# InterfaceConfiguracao.net
KiCad netlist of a schematic drawn in Altium Designer
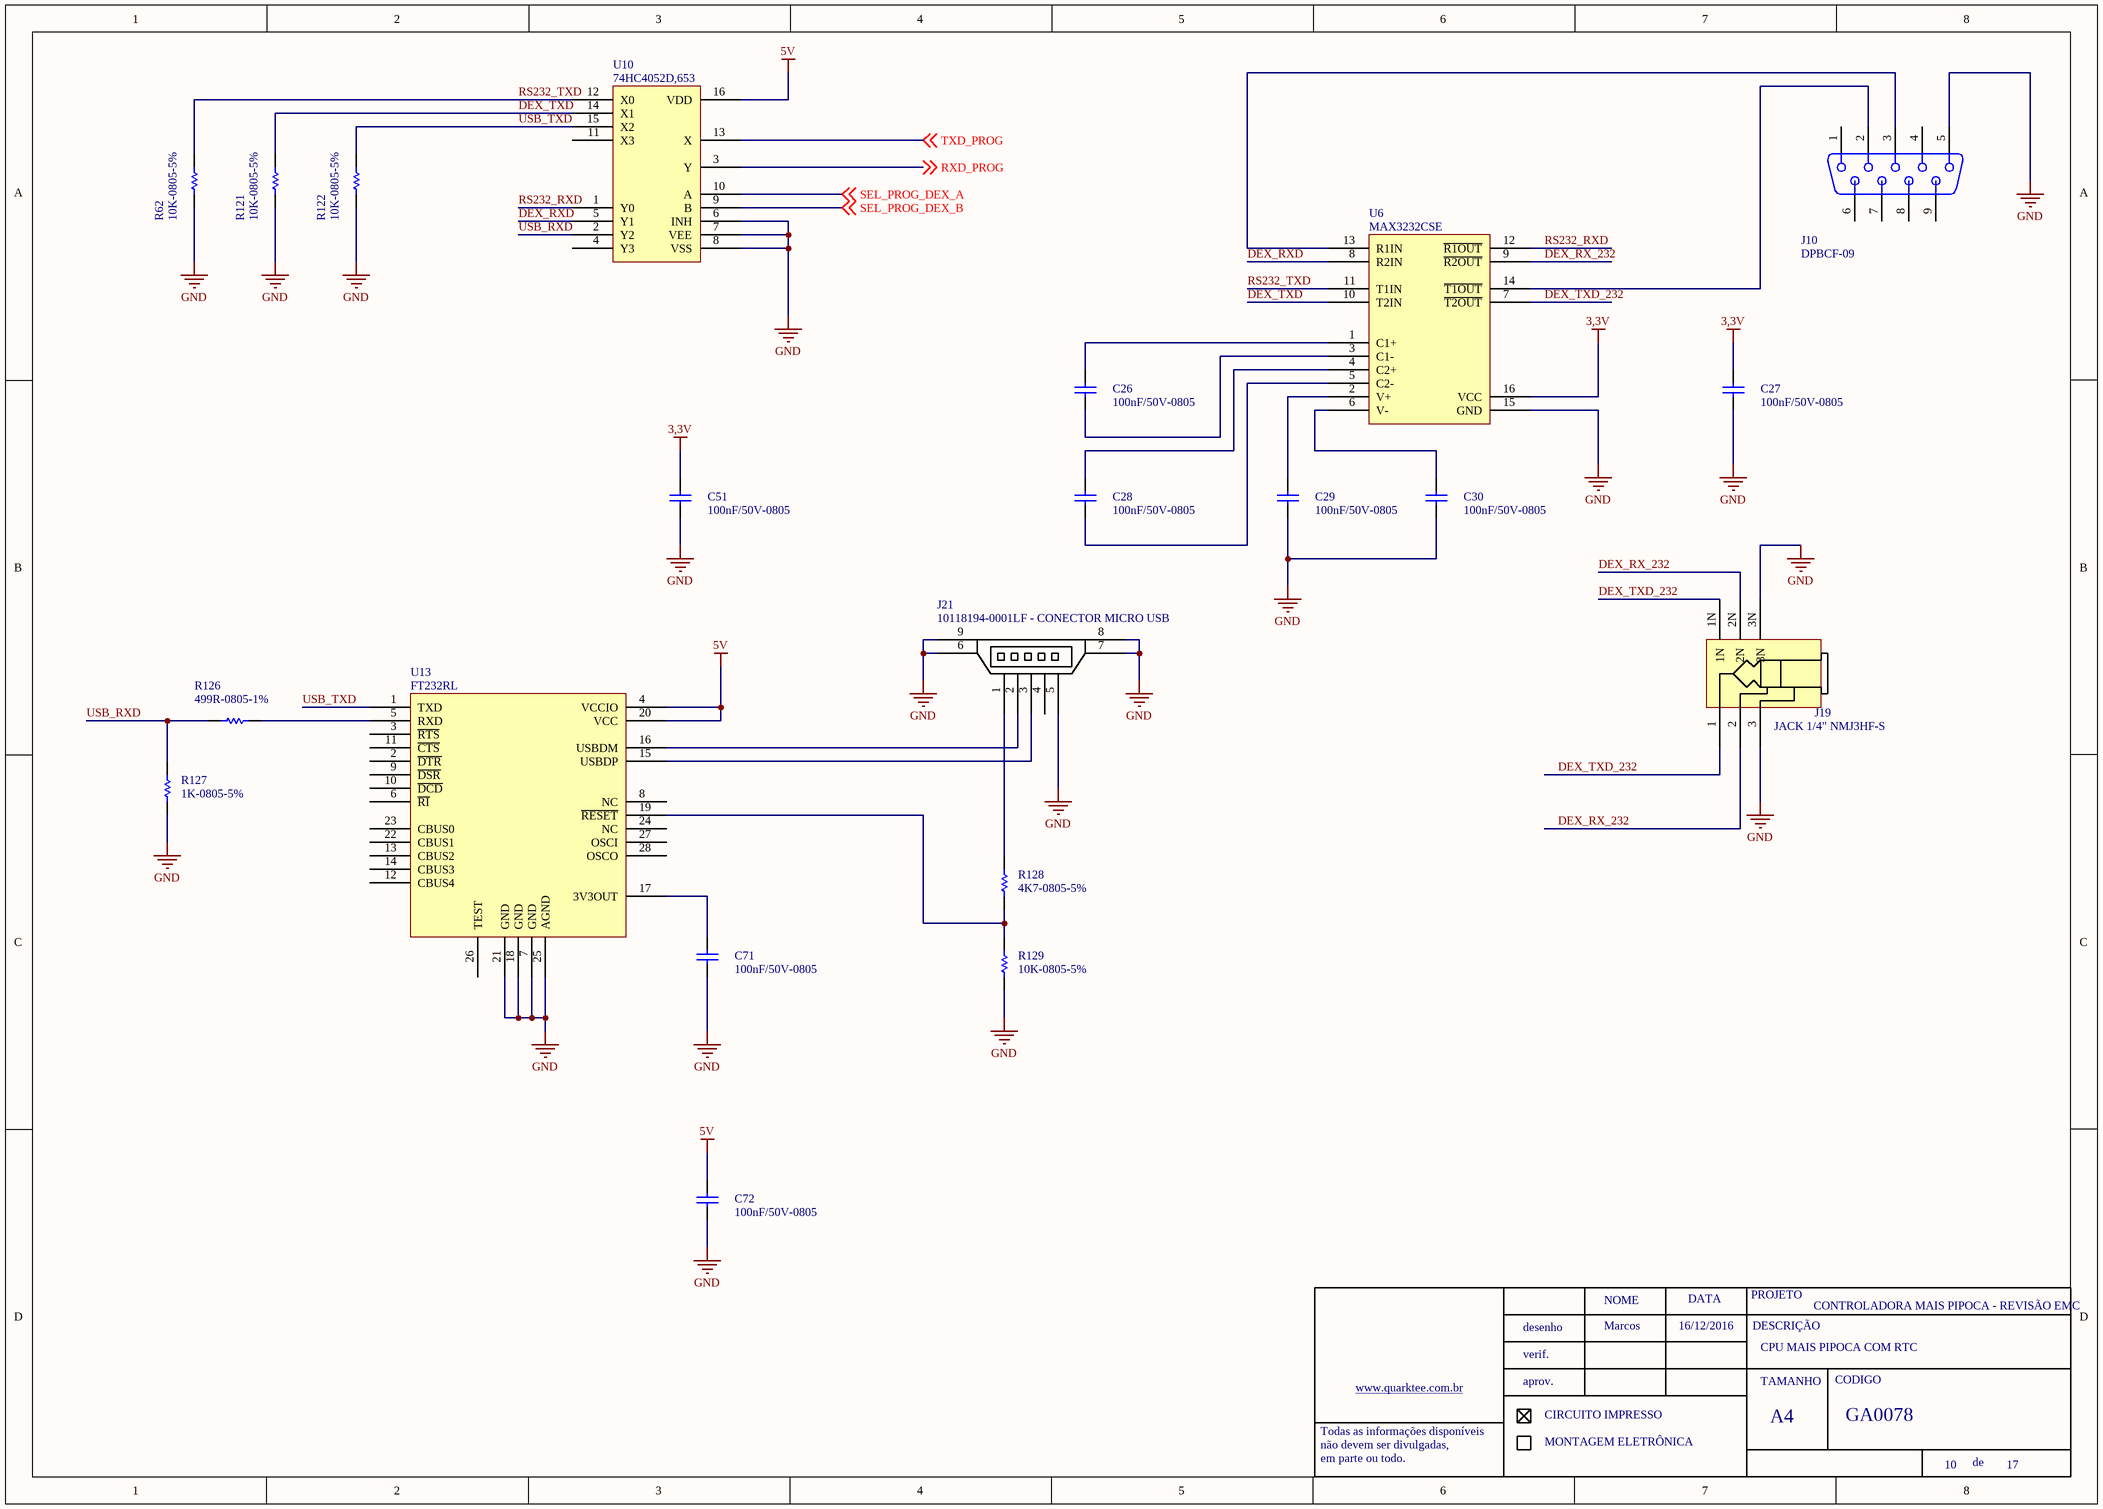
[diagram p0: InterfaceConfiguracao.SchDoc]

(export (version "E")
  (design (tool "Eeschema 10.0.6"))
  (components
    (comp (ref "C26")
      (value "100nF/50V-0805")
      (footprint "0805-REVISADO ONDA")
      (description "100nF/50-0805-NPO")
      (libsource (lib "AquinoLib") (part "100nF/50-0805-NPO"))
    )
    (comp (ref "C27")
      (value "100nF/50V-0805")
      (footprint "0805-REVISADO ONDA")
      (description "100nF/50-0805-NPO")
      (libsource (lib "AquinoLib") (part "100nF/50-0805-NPO"))
    )
    (comp (ref "C28")
      (value "100nF/50V-0805")
      (footprint "0805-REVISADO ONDA")
      (description "100nF/50-0805-NPO")
      (libsource (lib "AquinoLib") (part "100nF/50-0805-NPO"))
    )
    (comp (ref "C29")
      (value "100nF/50V-0805")
      (footprint "0805-REVISADO ONDA")
      (description "100nF/50-0805-NPO")
      (libsource (lib "AquinoLib") (part "100nF/50-0805-NPO"))
    )
    (comp (ref "C30")
      (value "100nF/50V-0805")
      (footprint "0805-REVISADO ONDA")
      (description "100nF/50-0805-NPO")
      (libsource (lib "AquinoLib") (part "100nF/50-0805-NPO"))
    )
    (comp (ref "C51")
      (value "100nF/50V-0805")
      (footprint "0805-REVISADO ONDA")
      (libsource (lib "AquinoLib") (part "100nF/50-0805-NPO"))
    )
    (comp (ref "C71")
      (value "100nF/50V-0805")
      (footprint "0805-REVISADO ONDA")
      (libsource (lib "AquinoLib") (part "100nF/50-0805-NPO"))
    )
    (comp (ref "C72")
      (value "100nF/50V-0805")
      (footprint "0805-REVISADO ONDA")
      (libsource (lib "AquinoLib") (part "100nF/50-0805-NPO"))
    )
    (comp (ref "J10")
      (value "DPBCF-09")
      (footprint "DB9-FÊMEA MONTAGEM EM PCI 180")
      (description "DBPCF-09")
      (libsource (lib "ChaveDigital3") (part "DB-9 - FÊMEA 180º MONTAGEM EM PCI"))
    )
    (comp (ref "J19")
      (value "JACK 1/4\" NMJ3HF-S")
      (description "NMJ3HF-S")
      (libsource (lib "AquinoLib") (part "NMJ3HF-S"))
    )
    (comp (ref "J21")
      (value "10118194-0001LF - CONECTOR MICRO USB")
      (libsource (lib "AquinoLib") (part "MINI_USB"))
    )
    (comp (ref "R62")
      (value "10K-0805-5%")
      (footprint "0805-REVISADO ONDA")
      (libsource (lib "AquinoLib") (part "10K-0805-5%"))
    )
    (comp (ref "R121")
      (value "10K-0805-5%")
      (footprint "0805-REVISADO ONDA")
      (libsource (lib "AquinoLib") (part "10K-0805-5%"))
    )
    (comp (ref "R122")
      (value "10K-0805-5%")
      (footprint "0805-REVISADO ONDA")
      (libsource (lib "AquinoLib") (part "10K-0805-5%"))
    )
    (comp (ref "R126")
      (value "499R-0805-1%")
      (footprint "0805-REVISADO ONDA")
      (description "1K-0805-5%")
      (libsource (lib "AquinoLib") (part "1K-0805-5%"))
    )
    (comp (ref "R127")
      (value "1K-0805-5%")
      (footprint "0805-REVISADO ONDA")
      (libsource (lib "AquinoLib") (part "1K-0805-5%"))
    )
    (comp (ref "R128")
      (value "4K7-0805-5%")
      (footprint "0805-REVISADO ONDA")
      (description "10K-0805-5%")
      (libsource (lib "AquinoLib") (part "10K-0805-5%"))
    )
    (comp (ref "R129")
      (value "10K-0805-5%")
      (footprint "0805-REVISADO ONDA")
      (libsource (lib "AquinoLib") (part "10K-0805-5%"))
    )
    (comp (ref "U6")
      (value "MAX3232CSE")
      (footprint "SOIC 16 PINOS")
      (libsource (lib "ChaveDigital3") (part "MAX3232CSE"))
    )
    (comp (ref "U10") (value "74HC4052D,653") (libsource (lib "AquinoLib") (part "CD74HC4052PWR")))
    (comp (ref "U13") (value "FT232RL") (libsource (lib "AquinoLib") (part "FT232RL")))
  )
  (nets
    (net (code "1") (name "/DEX_RXD") (class "Default")
      (node (ref "U10") (pin "5") (pinfunction "Y1_5") (pintype "passive"))
      (node (ref "U6") (pin "8") (pinfunction "R2IN_8") (pintype "passive"))
    )
    (net (code "2") (name "/DEX_RX_232") (class "Default")
      (node (ref "J19") (pin "2") (pinfunction "2_2") (pintype "passive"))
      (node (ref "J19") (pin "2N") (pinfunction "2N_2N") (pintype "passive"))
      (node (ref "U6") (pin "9") (pinfunction "~{R2OUT}_9") (pintype "passive"))
    )
    (net (code "3") (name "/DEX_TXD") (class "Default")
      (node (ref "R121") (pin "2") (pinfunction "2_2") (pintype "passive"))
      (node (ref "U10") (pin "14") (pinfunction "X1_14") (pintype "passive"))
      (node (ref "U6") (pin "10") (pinfunction "T2IN_10") (pintype "passive"))
    )
    (net (code "4") (name "/DEX_TXD_232") (class "Default")
      (node (ref "J19") (pin "1") (pinfunction "1_1") (pintype "passive"))
      (node (ref "J19") (pin "1N") (pinfunction "1N_1N") (pintype "passive"))
      (node (ref "U6") (pin "7") (pinfunction "~{T2OUT}_7") (pintype "passive"))
    )
    (net (code "5") (name "/RS232_RXD") (class "Default")
      (node (ref "U10") (pin "1") (pinfunction "Y0_1") (pintype "passive"))
      (node (ref "U6") (pin "12") (pinfunction "~{R1OUT}_12") (pintype "passive"))
    )
    (net (code "6") (name "/RS232_TXD") (class "Default")
      (node (ref "R62") (pin "2") (pinfunction "2_2") (pintype "passive"))
      (node (ref "U10") (pin "12") (pinfunction "X0_12") (pintype "passive"))
      (node (ref "U6") (pin "11") (pinfunction "T1IN_11") (pintype "passive"))
    )
    (net (code "7") (name "/USB_RXD") (class "Default")
      (node (ref "R126") (pin "1") (pinfunction "1_1") (pintype "passive"))
      (node (ref "R127") (pin "2") (pinfunction "2_2") (pintype "passive"))
      (node (ref "U10") (pin "2") (pinfunction "Y2_2") (pintype "passive"))
    )
    (net (code "8") (name "/USB_TXD") (class "Default")
      (node (ref "R122") (pin "2") (pinfunction "2_2") (pintype "passive"))
      (node (ref "U10") (pin "15") (pinfunction "X2_15") (pintype "passive"))
      (node (ref "U13") (pin "1") (pinfunction "TXD_1") (pintype "passive"))
    )
    (net (code "9") (name "3,3V") (class "Default")
      (node (ref "C27") (pin "2") (pinfunction "2_2") (pintype "passive"))
      (node (ref "C51") (pin "2") (pinfunction "2_2") (pintype "passive"))
      (node (ref "U6") (pin "16") (pinfunction "VCC_16") (pintype "passive"))
    )
    (net (code "10") (name "5V") (class "Default")
      (node (ref "C72") (pin "2") (pinfunction "2_2") (pintype "passive"))
      (node (ref "U10") (pin "16") (pinfunction "VDD_16") (pintype "passive"))
      (node (ref "U13") (pin "20") (pinfunction "VCC_20") (pintype "passive"))
      (node (ref "U13") (pin "4") (pinfunction "VCCIO_4") (pintype "passive"))
    )
    (net (code "11") (name "GND") (class "Default")
      (node (ref "C27") (pin "1") (pinfunction "1_1") (pintype "passive"))
      (node (ref "C29") (pin "1") (pinfunction "1_1") (pintype "passive"))
      (node (ref "C30") (pin "1") (pinfunction "1_1") (pintype "passive"))
      (node (ref "C51") (pin "1") (pinfunction "1_1") (pintype "passive"))
      (node (ref "C71") (pin "1") (pinfunction "1_1") (pintype "passive"))
      (node (ref "C72") (pin "1") (pinfunction "1_1") (pintype "passive"))
      (node (ref "J10") (pin "5") (pinfunction "5_5") (pintype "passive"))
      (node (ref "J19") (pin "3") (pinfunction "3_3") (pintype "passive"))
      (node (ref "J19") (pin "3N") (pinfunction "3N_3N") (pintype "passive"))
      (node (ref "J21") (pin "5") (pinfunction "5_5") (pintype "passive"))
      (node (ref "J21") (pin "6") (pinfunction "6_6") (pintype "passive"))
      (node (ref "J21") (pin "7") (pinfunction "7_7") (pintype "passive"))
      (node (ref "J21") (pin "8") (pinfunction "8_8") (pintype "passive"))
      (node (ref "J21") (pin "9") (pinfunction "9_9") (pintype "passive"))
      (node (ref "R121") (pin "1") (pinfunction "1_1") (pintype "passive"))
      (node (ref "R122") (pin "1") (pinfunction "1_1") (pintype "passive"))
      (node (ref "R127") (pin "1") (pinfunction "1_1") (pintype "passive"))
      (node (ref "R129") (pin "1") (pinfunction "1_1") (pintype "passive"))
      (node (ref "R62") (pin "1") (pinfunction "1_1") (pintype "passive"))
      (node (ref "U10") (pin "6") (pinfunction "INH_6") (pintype "passive"))
      (node (ref "U10") (pin "7") (pinfunction "VEE_7") (pintype "passive"))
      (node (ref "U10") (pin "8") (pinfunction "VSS_8") (pintype "passive"))
      (node (ref "U13") (pin "18") (pinfunction "GND_18") (pintype "passive"))
      (node (ref "U13") (pin "21") (pinfunction "GND_21") (pintype "passive"))
      (node (ref "U13") (pin "25") (pinfunction "AGND_25") (pintype "passive"))
      (node (ref "U13") (pin "7") (pinfunction "GND_7") (pintype "passive"))
      (node (ref "U6") (pin "15") (pinfunction "GND_15") (pintype "passive"))
    )
    (net (code "12") (name "Net-(J21-Pad1)") (class "Default")
      (node (ref "J21") (pin "1") (pinfunction "1_1") (pintype "passive"))
      (node (ref "R128") (pin "2") (pinfunction "2_2") (pintype "passive"))
    )
    (net (code "13") (name "Net-(U6-C1+)") (class "Default")
      (node (ref "C26") (pin "2") (pinfunction "2_2") (pintype "passive"))
      (node (ref "U6") (pin "1") (pinfunction "C1+_1") (pintype "passive"))
    )
    (net (code "14") (name "Net-(U6-C1-)") (class "Default")
      (node (ref "C26") (pin "1") (pinfunction "1_1") (pintype "passive"))
      (node (ref "U6") (pin "3") (pinfunction "C1-_3") (pintype "passive"))
    )
    (net (code "15") (name "Net-(U6-C2+)") (class "Default")
      (node (ref "C28") (pin "2") (pinfunction "2_2") (pintype "passive"))
      (node (ref "U6") (pin "4") (pinfunction "C2+_4") (pintype "passive"))
    )
    (net (code "16") (name "Net-(U6-C2-)") (class "Default")
      (node (ref "C28") (pin "1") (pinfunction "1_1") (pintype "passive"))
      (node (ref "U6") (pin "5") (pinfunction "C2-_5") (pintype "passive"))
    )
    (net (code "17") (name "Net-(U6-R1IN)") (class "Default")
      (node (ref "J10") (pin "3") (pinfunction "3_3") (pintype "passive"))
      (node (ref "U6") (pin "13") (pinfunction "R1IN_13") (pintype "passive"))
    )
    (net (code "18") (name "Net-(U6-V+)") (class "Default")
      (node (ref "C29") (pin "2") (pinfunction "2_2") (pintype "passive"))
      (node (ref "U6") (pin "2") (pinfunction "V+_2") (pintype "passive"))
    )
    (net (code "19") (name "Net-(U6-V-)") (class "Default")
      (node (ref "C30") (pin "2") (pinfunction "2_2") (pintype "passive"))
      (node (ref "U6") (pin "6") (pinfunction "V-_6") (pintype "passive"))
    )
    (net (code "20") (name "Net-(U6-~{T1OUT})") (class "Default")
      (node (ref "J10") (pin "2") (pinfunction "2_2") (pintype "passive"))
      (node (ref "U6") (pin "14") (pinfunction "~{T1OUT}_14") (pintype "passive"))
    )
    (net (code "21") (name "Net-(U13-3V3OUT)") (class "Default")
      (node (ref "C71") (pin "2") (pinfunction "2_2") (pintype "passive"))
      (node (ref "U13") (pin "17") (pinfunction "3V3OUT_17") (pintype "passive"))
    )
    (net (code "22") (name "Net-(U13-RXD)") (class "Default")
      (node (ref "R126") (pin "2") (pinfunction "2_2") (pintype "passive"))
      (node (ref "U13") (pin "5") (pinfunction "RXD_5") (pintype "passive"))
    )
    (net (code "23") (name "Net-(U13-USBDM)") (class "Default")
      (node (ref "J21") (pin "2") (pinfunction "2_2") (pintype "passive"))
      (node (ref "U13") (pin "16") (pinfunction "USBDM_16") (pintype "passive"))
    )
    (net (code "24") (name "Net-(U13-USBDP)") (class "Default")
      (node (ref "J21") (pin "3") (pinfunction "3_3") (pintype "passive"))
      (node (ref "U13") (pin "15") (pinfunction "USBDP_15") (pintype "passive"))
    )
    (net (code "25") (name "Net-(U13-~{RESET})") (class "Default")
      (node (ref "R128") (pin "1") (pinfunction "1_1") (pintype "passive"))
      (node (ref "R129") (pin "2") (pinfunction "2_2") (pintype "passive"))
      (node (ref "U13") (pin "19") (pinfunction "~{RESET}_19") (pintype "passive"))
    )
    (net (code "26") (name "RXD_PROG") (class "Default")
      (node (ref "U10") (pin "3") (pinfunction "Y_3") (pintype "passive"))
    )
    (net (code "27") (name "SEL_PROG_DEX_A") (class "Default")
      (node (ref "U10") (pin "10") (pinfunction "A_10") (pintype "passive"))
    )
    (net (code "28") (name "SEL_PROG_DEX_B") (class "Default")
      (node (ref "U10") (pin "9") (pinfunction "B_9") (pintype "passive"))
    )
    (net (code "29") (name "TXD_PROG") (class "Default")
      (node (ref "U10") (pin "13") (pinfunction "X_13") (pintype "passive"))
    )
    (net (code "30") (name "unconnected-(J10-Pad1)") (class "Default")
      (node (ref "J10") (pin "1") (pinfunction "1_1") (pintype "passive"))
    )
    (net (code "31") (name "unconnected-(J10-Pad4)") (class "Default")
      (node (ref "J10") (pin "4") (pinfunction "4_4") (pintype "passive"))
    )
    (net (code "32") (name "unconnected-(J10-Pad6)") (class "Default")
      (node (ref "J10") (pin "6") (pinfunction "6_6") (pintype "passive"))
    )
    (net (code "33") (name "unconnected-(J10-Pad7)") (class "Default")
      (node (ref "J10") (pin "7") (pinfunction "7_7") (pintype "passive"))
    )
    (net (code "34") (name "unconnected-(J10-Pad8)") (class "Default")
      (node (ref "J10") (pin "8") (pinfunction "8_8") (pintype "passive"))
    )
    (net (code "35") (name "unconnected-(J10-Pad9)") (class "Default")
      (node (ref "J10") (pin "9") (pinfunction "9_9") (pintype "passive"))
    )
    (net (code "36") (name "unconnected-(J21-Pad4)") (class "Default")
      (node (ref "J21") (pin "4") (pinfunction "4_4") (pintype "passive"))
    )
    (net (code "37") (name "unconnected-(U10-X3-Pad11)") (class "Default")
      (node (ref "U10") (pin "11") (pinfunction "X3_11") (pintype "passive"))
    )
    (net (code "38") (name "unconnected-(U10-Y3-Pad4)") (class "Default")
      (node (ref "U10") (pin "4") (pinfunction "Y3_4") (pintype "passive"))
    )
    (net (code "39") (name "unconnected-(U13-CBUS0-Pad23)") (class "Default")
      (node (ref "U13") (pin "23") (pinfunction "CBUS0_23") (pintype "passive"))
    )
    (net (code "40") (name "unconnected-(U13-CBUS1-Pad22)") (class "Default")
      (node (ref "U13") (pin "22") (pinfunction "CBUS1_22") (pintype "passive"))
    )
    (net (code "41") (name "unconnected-(U13-CBUS2-Pad13)") (class "Default")
      (node (ref "U13") (pin "13") (pinfunction "CBUS2_13") (pintype "passive"))
    )
    (net (code "42") (name "unconnected-(U13-CBUS3-Pad14)") (class "Default")
      (node (ref "U13") (pin "14") (pinfunction "CBUS3_14") (pintype "passive"))
    )
    (net (code "43") (name "unconnected-(U13-CBUS4-Pad12)") (class "Default")
      (node (ref "U13") (pin "12") (pinfunction "CBUS4_12") (pintype "passive"))
    )
    (net (code "44") (name "unconnected-(U13-NC-Pad8)") (class "Default")
      (node (ref "U13") (pin "8") (pinfunction "NC_8") (pintype "passive"))
    )
    (net (code "45") (name "unconnected-(U13-NC-Pad24)") (class "Default")
      (node (ref "U13") (pin "24") (pinfunction "NC_24") (pintype "passive"))
    )
    (net (code "46") (name "unconnected-(U13-OSCI-Pad27)") (class "Default")
      (node (ref "U13") (pin "27") (pinfunction "OSCI_27") (pintype "passive"))
    )
    (net (code "47") (name "unconnected-(U13-OSCO-Pad28)") (class "Default")
      (node (ref "U13") (pin "28") (pinfunction "OSCO_28") (pintype "passive"))
    )
    (net (code "48") (name "unconnected-(U13-TEST-Pad26)") (class "Default")
      (node (ref "U13") (pin "26") (pinfunction "TEST_26") (pintype "passive"))
    )
    (net (code "49") (name "unconnected-(U13-~{CTS}-Pad11)") (class "Default")
      (node (ref "U13") (pin "11") (pinfunction "~{CTS}_11") (pintype "passive"))
    )
    (net (code "50") (name "unconnected-(U13-~{DCD}-Pad10)") (class "Default")
      (node (ref "U13") (pin "10") (pinfunction "~{DCD}_10") (pintype "passive"))
    )
    (net (code "51") (name "unconnected-(U13-~{DSR}-Pad9)") (class "Default")
      (node (ref "U13") (pin "9") (pinfunction "~{DSR}_9") (pintype "passive"))
    )
    (net (code "52") (name "unconnected-(U13-~{DTR}-Pad2)") (class "Default")
      (node (ref "U13") (pin "2") (pinfunction "~{DTR}_2") (pintype "passive"))
    )
    (net (code "53") (name "unconnected-(U13-~{RI}-Pad6)") (class "Default")
      (node (ref "U13") (pin "6") (pinfunction "~{RI}_6") (pintype "passive"))
    )
    (net (code "54") (name "unconnected-(U13-~{RTS}-Pad3)") (class "Default")
      (node (ref "U13") (pin "3") (pinfunction "~{RTS}_3") (pintype "passive"))
    )
  )
)
